# BSPD_Final_1.net
KiCad netlist of a schematic drawn in EAGLE
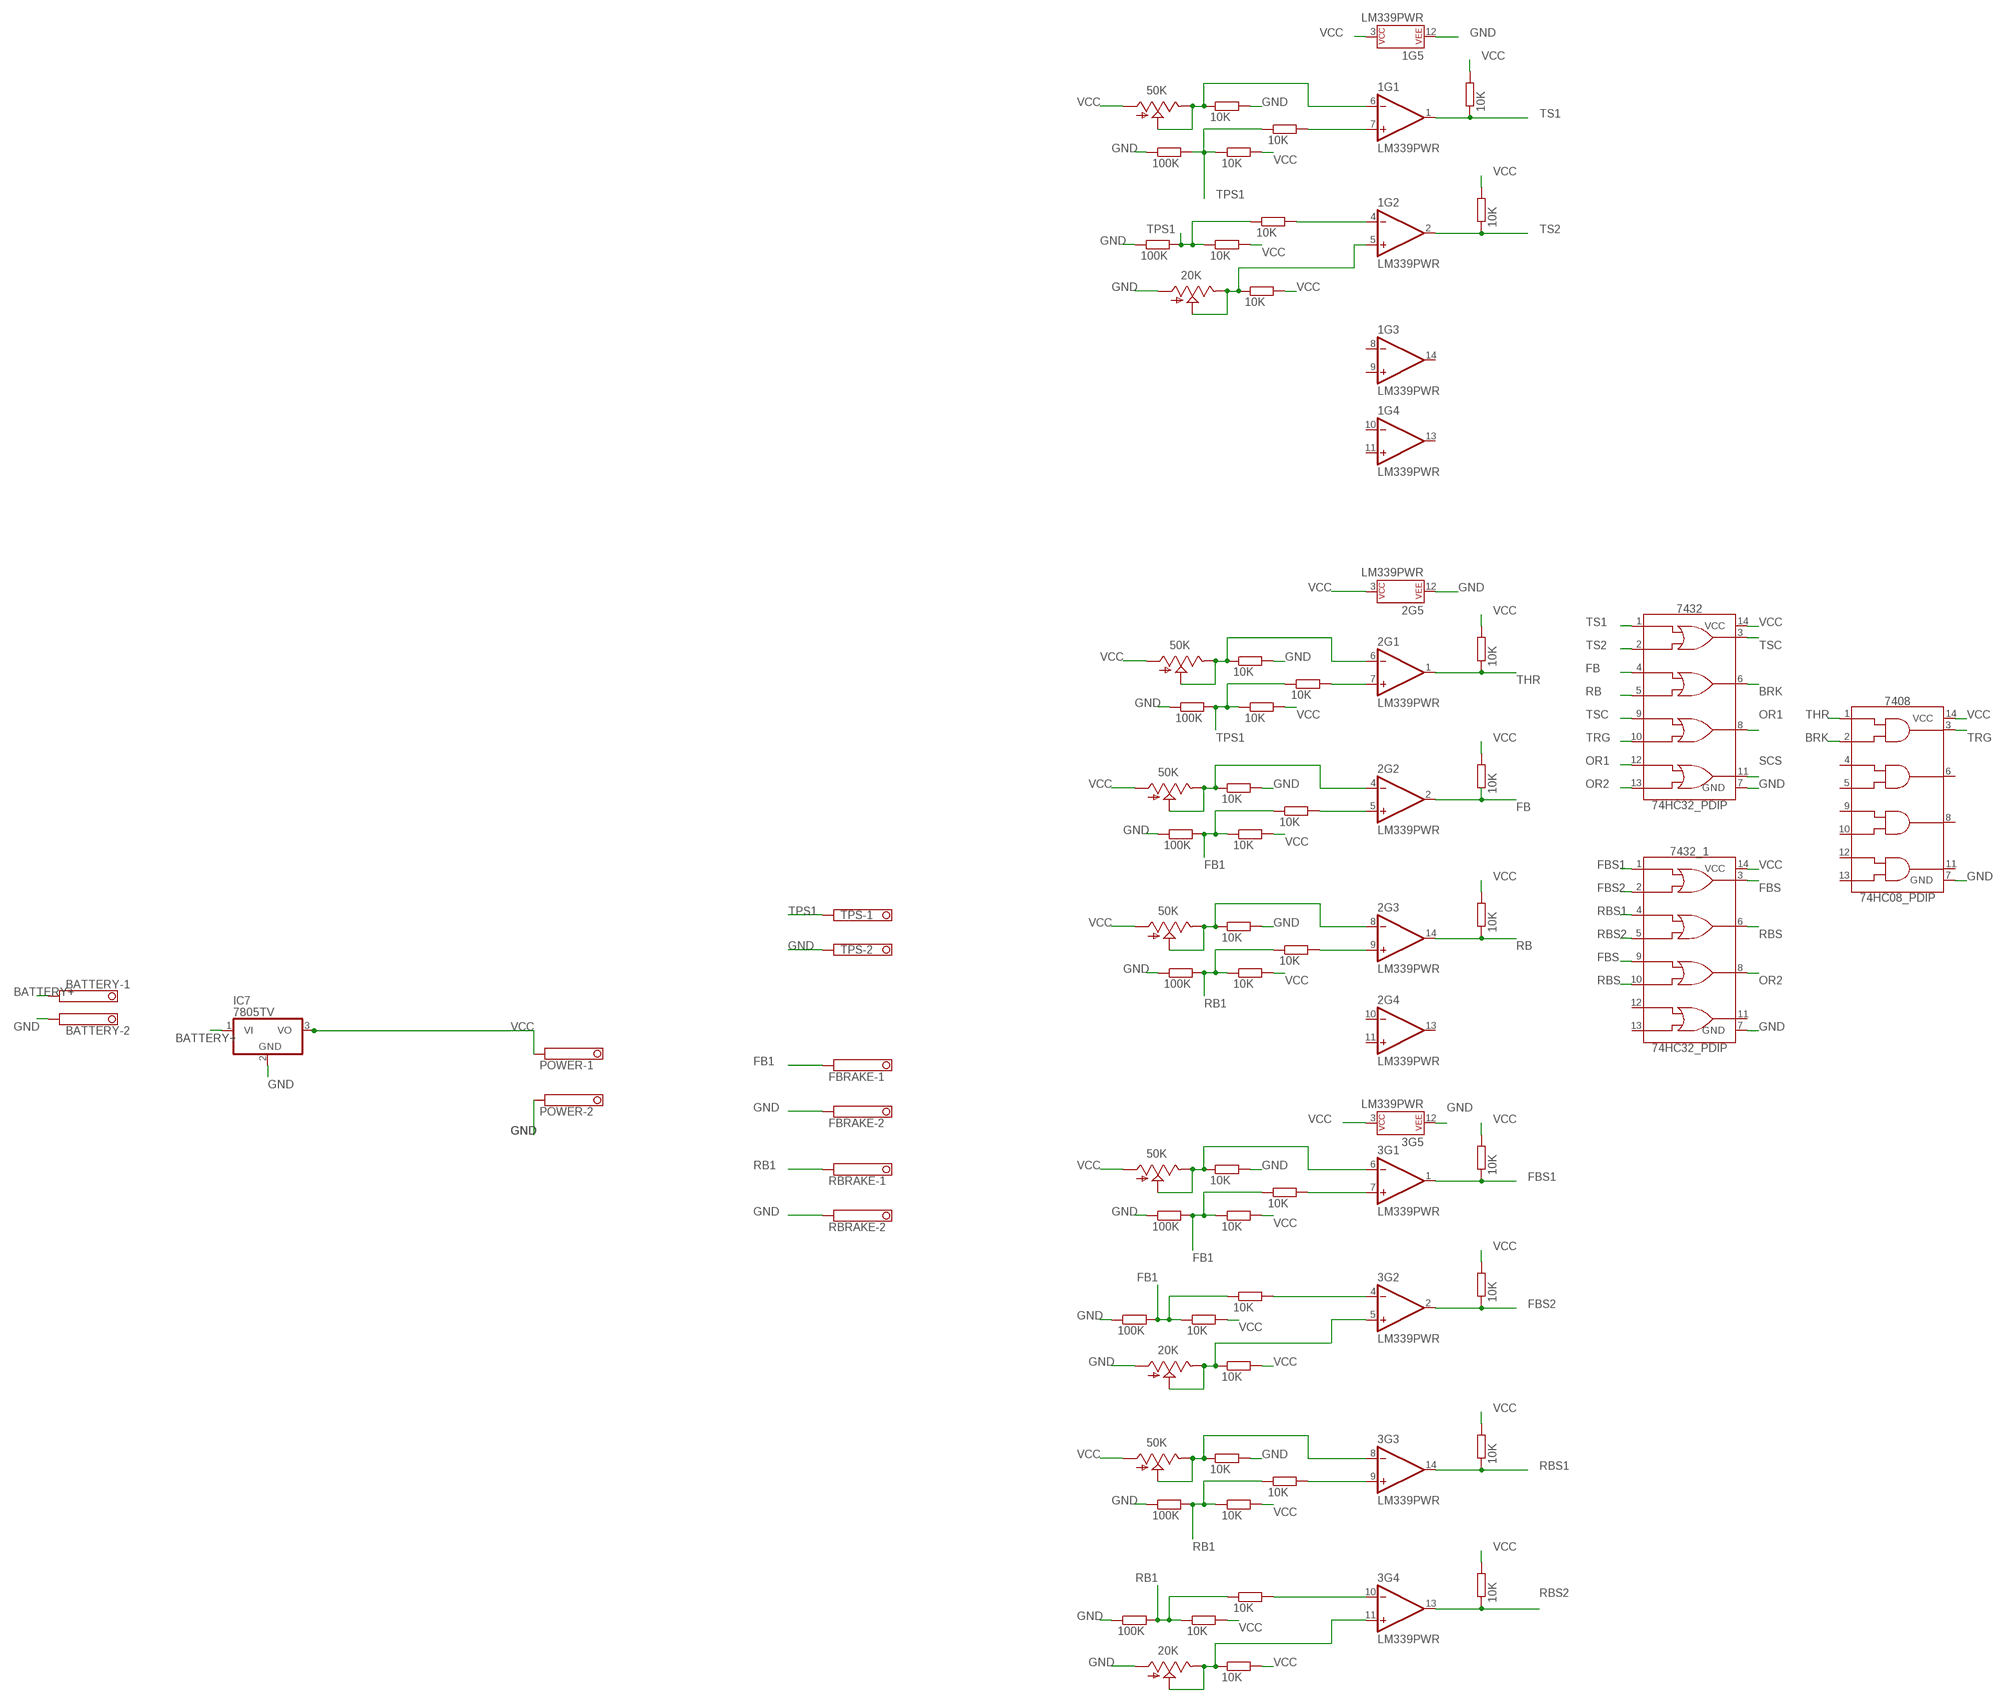
[diagram p0: schematic, sheet 1, part 1 of 2]
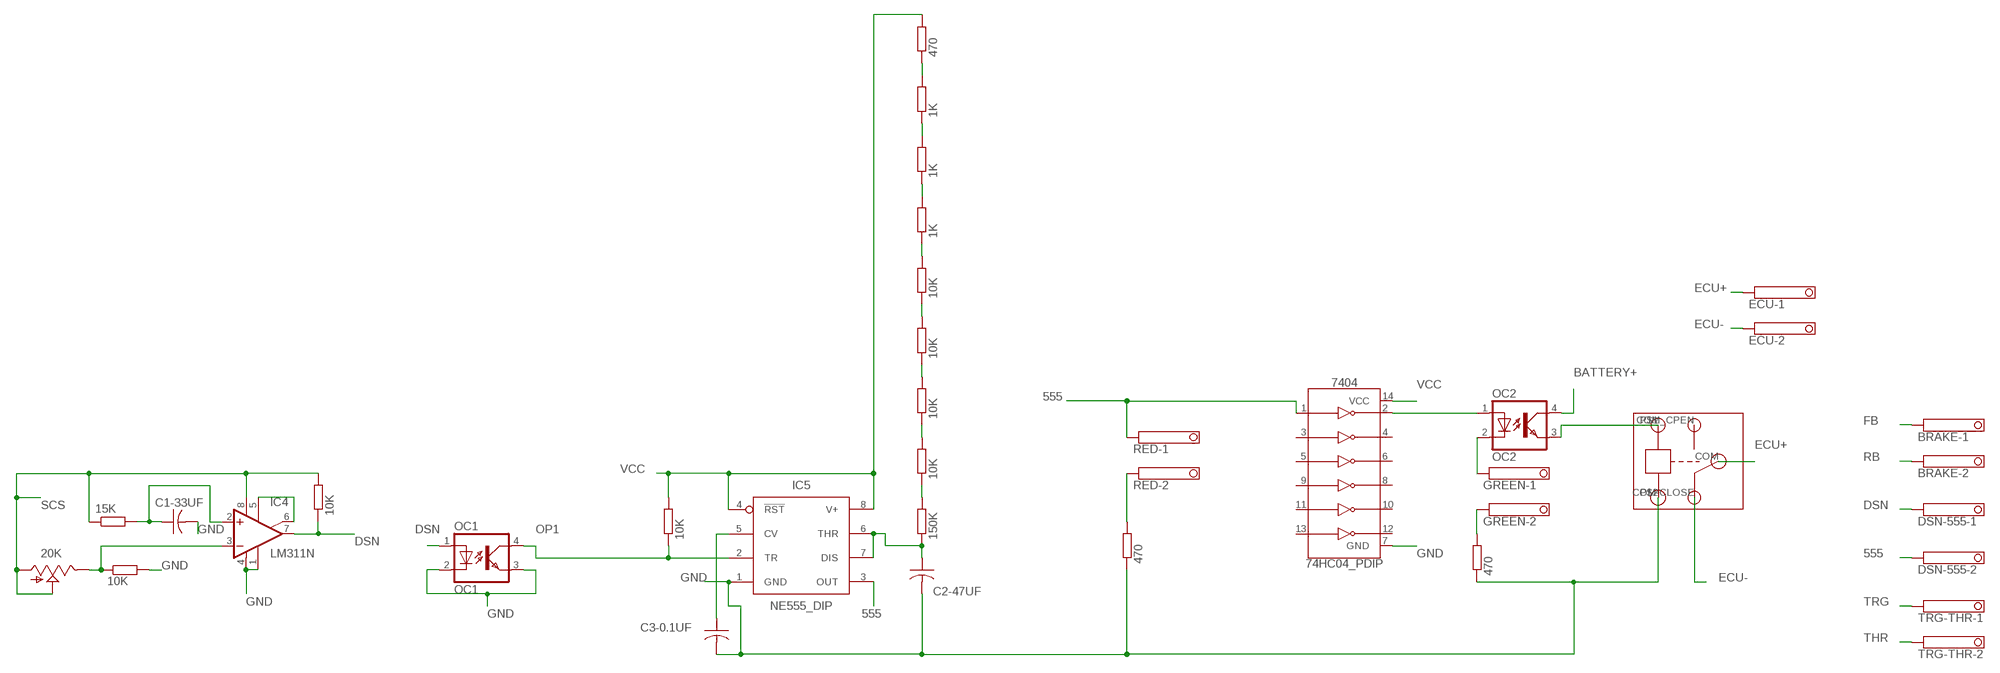
[diagram p1: schematic, sheet 1, part 2 of 2]

(export (version "E")
  (design (tool "Eeschema 10.0.6"))
  (components
    (comp (ref "1")
      (value "LM339PWR")
      (footprint "eagle-import:TSSOP-14")
      (libsource (lib "eagle-import") (part "LM339"))
    )
    (comp (ref "2")
      (value "LM339PWR")
      (footprint "eagle-import:TSSOP-14")
      (libsource (lib "eagle-import") (part "LM339"))
    )
    (comp (ref "3")
      (value "LM339PWR")
      (footprint "eagle-import:TSSOP-14")
      (libsource (lib "eagle-import") (part "LM339"))
    )
    (comp (ref "50K9")
      (value "20K")
      (footprint "eagle-import:B64Y")
      (libsource (lib "eagle-import") (part "TRIM_US-B64Y"))
    )
    (comp (ref "555RES1")
      (value "150K")
      (footprint "eagle-import:0207_10")
      (libsource (lib "eagle-import") (part "R-EU_0207/10"))
    )
    (comp (ref "555RES2")
      (value "10K")
      (footprint "eagle-import:0207_10")
      (libsource (lib "eagle-import") (part "R-EU_0207/10"))
    )
    (comp (ref "555RES3")
      (value "10K")
      (footprint "eagle-import:0207_10")
      (libsource (lib "eagle-import") (part "R-EU_0207/10"))
    )
    (comp (ref "555RES4")
      (value "10K")
      (footprint "eagle-import:0207_10")
      (libsource (lib "eagle-import") (part "R-EU_0207/10"))
    )
    (comp (ref "555RES5")
      (value "10K")
      (footprint "eagle-import:0207_10")
      (libsource (lib "eagle-import") (part "R-EU_0207/10"))
    )
    (comp (ref "555RES6")
      (value "1K")
      (footprint "eagle-import:0207_10")
      (libsource (lib "eagle-import") (part "R-EU_0207/10"))
    )
    (comp (ref "555RES7")
      (value "1K")
      (footprint "eagle-import:0207_10")
      (libsource (lib "eagle-import") (part "R-EU_0207/10"))
    )
    (comp (ref "555RES8")
      (value "1K")
      (footprint "eagle-import:0207_10")
      (libsource (lib "eagle-import") (part "R-EU_0207/10"))
    )
    (comp (ref "555RES9")
      (value "470")
      (footprint "eagle-import:0207_10")
      (libsource (lib "eagle-import") (part "R-EU_0207/10"))
    )
    (comp (ref "7404")
      (value "74HC04_PDIP")
      (footprint "eagle-import:DIP762W53P254L1969H508Q14B")
      (fields (field (name "MANUFACTURER") "Generic"))
      (libsource (lib "eagle-import") (part "74HC04_PDIP"))
    )
    (comp (ref "7408")
      (value "74HC08_PDIP")
      (footprint "eagle-import:DIP762W53P254L1969H508Q14B")
      (fields (field (name "MANUFACTURER") "Generic"))
      (libsource (lib "eagle-import") (part "74HC08_PDIP"))
    )
    (comp (ref "7432")
      (value "74HC32_PDIP")
      (footprint "eagle-import:DIP762W53P254L1969H508Q14B")
      (fields (field (name "MANUFACTURER") "Generic"))
      (libsource (lib "eagle-import") (part "74HC32_PDIP"))
    )
    (comp (ref "7432_1")
      (value "74HC32_PDIP")
      (footprint "eagle-import:DIP762W53P254L1969H508Q14B")
      (fields (field (name "MANUFACTURER") "Generic"))
      (libsource (lib "eagle-import") (part "74HC32_PDIP"))
    )
    (comp (ref "BATTERY")
      (value "TERMINAL-BLOCK-3.5MM-2-PIN-ROUND-PAD")
      (footprint "eagle-import:TERMINAL-BLOCK-2-PIN-3.5MM-ROUND-PAD")
      (libsource (lib "eagle-import") (part "TERMINAL-BLOCK-3.5MM-2-PIN-ROUND-PAD"))
    )
    (comp (ref "BRAKE")
      (value "TERMINAL-BLOCK-3.5MM-2-PIN-ROUND-PAD")
      (footprint "eagle-import:TERMINAL-BLOCK-2-PIN-3.5MM-ROUND-PAD")
      (libsource (lib "eagle-import") (part "TERMINAL-BLOCK-3.5MM-2-PIN-ROUND-PAD"))
    )
    (comp (ref "C1-33UF")
      (value "33uF")
      (footprint "eagle-import:CAP_RADIAL_2MM")
      (fields
        (field (name "DIGIKEY_PART_NUMBER") "P5179-ND")
        (field (name "MANUFACTURER") "Panasonic Electronic Components")
        (field (name "MPN") "ECA-1HM220")
        (field (name "CREATED_BY") "PCBLayout.com")
      )
      (libsource (lib "eagle-import") (part "ECA-1HM220"))
    )
    (comp (ref "C2-47UF")
      (value "33uF")
      (footprint "eagle-import:CAP_RADIAL_2MM")
      (fields
        (field (name "DIGIKEY_PART_NUMBER") "P5179-ND")
        (field (name "MANUFACTURER") "Panasonic Electronic Components")
        (field (name "MPN") "ECA-1HM220")
        (field (name "CREATED_BY") "PCBLayout.com")
      )
      (libsource (lib "eagle-import") (part "ECA-1HM220"))
    )
    (comp (ref "C3-0.1UF")
      (value "33uF")
      (footprint "eagle-import:CAP_RADIAL_2MM")
      (fields
        (field (name "DIGIKEY_PART_NUMBER") "P5179-ND")
        (field (name "MANUFACTURER") "Panasonic Electronic Components")
        (field (name "MPN") "ECA-1HM220")
        (field (name "CREATED_BY") "PCBLayout.com")
      )
      (libsource (lib "eagle-import") (part "ECA-1HM220"))
    )
    (comp (ref "DCNPULL")
      (value "10K")
      (footprint "eagle-import:0207_10")
      (libsource (lib "eagle-import") (part "R-EU_0207/10"))
    )
    (comp (ref "DCNRES1")
      (value "15K")
      (footprint "eagle-import:0207_10")
      (libsource (lib "eagle-import") (part "R-EU_0207/10"))
    )
    (comp (ref "DCNRES2")
      (value "10K")
      (footprint "eagle-import:0207_10")
      (libsource (lib "eagle-import") (part "R-EU_0207/10"))
    )
    (comp (ref "DSN-555")
      (value "TERMINAL-BLOCK-3.5MM-2-PIN-ROUND-PAD")
      (footprint "eagle-import:TERMINAL-BLOCK-2-PIN-3.5MM-ROUND-PAD")
      (libsource (lib "eagle-import") (part "TERMINAL-BLOCK-3.5MM-2-PIN-ROUND-PAD"))
    )
    (comp (ref "ECU")
      (value "TERMINAL-BLOCK-3.5MM-2-PIN-ROUND-PAD")
      (footprint "eagle-import:TERMINAL-BLOCK-2-PIN-3.5MM-ROUND-PAD")
      (libsource (lib "eagle-import") (part "TERMINAL-BLOCK-3.5MM-2-PIN-ROUND-PAD"))
    )
    (comp (ref "FBRAKE")
      (value "TERMINAL-BLOCK-3.5MM-2-PIN-ROUND-PAD")
      (footprint "eagle-import:TERMINAL-BLOCK-2-PIN-3.5MM-ROUND-PAD")
      (libsource (lib "eagle-import") (part "TERMINAL-BLOCK-3.5MM-2-PIN-ROUND-PAD"))
    )
    (comp (ref "GREEN")
      (value "TERMINAL-BLOCK-3.5MM-2-PIN-ROUND-PAD")
      (footprint "eagle-import:TERMINAL-BLOCK-2-PIN-3.5MM-ROUND-PAD")
      (libsource (lib "eagle-import") (part "TERMINAL-BLOCK-3.5MM-2-PIN-ROUND-PAD"))
    )
    (comp (ref "IC4")
      (value "LM311N")
      (footprint "eagle-import:DIL08")
      (libsource (lib "eagle-import") (part "LM311N"))
    )
    (comp (ref "IC5")
      (value "NE555_DIP")
      (footprint "eagle-import:DIP826W53P254L959H508Q8B")
      (fields (field (name "MANUFACTURER") "Texas Instruments ") (field (name "MPN") "NE555P "))
      (libsource (lib "eagle-import") (part "555_DIPNE"))
    )
    (comp (ref "IC7")
      (value "7805TV")
      (footprint "eagle-import:TO220V")
      (libsource (lib "eagle-import") (part "78TV05"))
    )
    (comp (ref "OC1")
      (value "OC1")
      (footprint "eagle-import:DIL04")
      (libsource (lib "eagle-import") (part "PC817"))
    )
    (comp (ref "OC2")
      (value "OC2")
      (footprint "eagle-import:DIL04")
      (libsource (lib "eagle-import") (part "PC817"))
    )
    (comp (ref "OCTPULL")
      (value "10K")
      (footprint "eagle-import:0207_10")
      (libsource (lib "eagle-import") (part "R-EU_0207/10"))
    )
    (comp (ref "POT1")
      (value "50K")
      (footprint "eagle-import:B64Y")
      (libsource (lib "eagle-import") (part "TRIM_US-B64Y"))
    )
    (comp (ref "POT2")
      (value "20K")
      (footprint "eagle-import:B64Y")
      (libsource (lib "eagle-import") (part "TRIM_US-B64Y"))
    )
    (comp (ref "POT3")
      (value "50K")
      (footprint "eagle-import:B64Y")
      (libsource (lib "eagle-import") (part "TRIM_US-B64Y"))
    )
    (comp (ref "POT4")
      (value "50K")
      (footprint "eagle-import:B64Y")
      (libsource (lib "eagle-import") (part "TRIM_US-B64Y"))
    )
    (comp (ref "POT5")
      (value "50K")
      (footprint "eagle-import:B64Y")
      (libsource (lib "eagle-import") (part "TRIM_US-B64Y"))
    )
    (comp (ref "POT6")
      (value "50K")
      (footprint "eagle-import:B64Y")
      (libsource (lib "eagle-import") (part "TRIM_US-B64Y"))
    )
    (comp (ref "POT7")
      (value "20K")
      (footprint "eagle-import:B64Y")
      (libsource (lib "eagle-import") (part "TRIM_US-B64Y"))
    )
    (comp (ref "POT8")
      (value "50K")
      (footprint "eagle-import:B64Y")
      (libsource (lib "eagle-import") (part "TRIM_US-B64Y"))
    )
    (comp (ref "POT9")
      (value "20K")
      (footprint "eagle-import:B64Y")
      (libsource (lib "eagle-import") (part "TRIM_US-B64Y"))
    )
    (comp (ref "POWER")
      (value "TERMINAL-BLOCK-3.5MM-2-PIN-ROUND-PAD")
      (footprint "eagle-import:TERMINAL-BLOCK-2-PIN-3.5MM-ROUND-PAD")
      (libsource (lib "eagle-import") (part "TERMINAL-BLOCK-3.5MM-2-PIN-ROUND-PAD"))
    )
    (comp (ref "PULL1")
      (value "10K")
      (footprint "eagle-import:0207_10")
      (libsource (lib "eagle-import") (part "R-EU_0207/10"))
    )
    (comp (ref "PULL2")
      (value "10K")
      (footprint "eagle-import:0207_10")
      (libsource (lib "eagle-import") (part "R-EU_0207/10"))
    )
    (comp (ref "PULL3")
      (value "10K")
      (footprint "eagle-import:0207_10")
      (libsource (lib "eagle-import") (part "R-EU_0207/10"))
    )
    (comp (ref "PULL4")
      (value "10K")
      (footprint "eagle-import:0207_10")
      (libsource (lib "eagle-import") (part "R-EU_0207/10"))
    )
    (comp (ref "PULL5")
      (value "10K")
      (footprint "eagle-import:0207_10")
      (libsource (lib "eagle-import") (part "R-EU_0207/10"))
    )
    (comp (ref "PULL6")
      (value "10K")
      (footprint "eagle-import:0207_10")
      (libsource (lib "eagle-import") (part "R-EU_0207/10"))
    )
    (comp (ref "PULL7")
      (value "10K")
      (footprint "eagle-import:0207_10")
      (libsource (lib "eagle-import") (part "R-EU_0207/10"))
    )
    (comp (ref "PULL8")
      (value "10K")
      (footprint "eagle-import:0207_10")
      (libsource (lib "eagle-import") (part "R-EU_0207/10"))
    )
    (comp (ref "PULL9")
      (value "10K")
      (footprint "eagle-import:0207_10")
      (libsource (lib "eagle-import") (part "R-EU_0207/10"))
    )
    (comp (ref "R56")
      (value "470")
      (footprint "eagle-import:0207_10")
      (libsource (lib "eagle-import") (part "R-EU_0207/10"))
    )
    (comp (ref "R57")
      (value "470")
      (footprint "eagle-import:0207_10")
      (libsource (lib "eagle-import") (part "R-EU_0207/10"))
    )
    (comp (ref "RBRAKE")
      (value "TERMINAL-BLOCK-3.5MM-2-PIN-ROUND-PAD")
      (footprint "eagle-import:TERMINAL-BLOCK-2-PIN-3.5MM-ROUND-PAD")
      (libsource (lib "eagle-import") (part "TERMINAL-BLOCK-3.5MM-2-PIN-ROUND-PAD"))
    )
    (comp (ref "RED")
      (value "TERMINAL-BLOCK-3.5MM-2-PIN-ROUND-PAD")
      (footprint "eagle-import:TERMINAL-BLOCK-2-PIN-3.5MM-ROUND-PAD")
      (libsource (lib "eagle-import") (part "TERMINAL-BLOCK-3.5MM-2-PIN-ROUND-PAD"))
    )
    (comp (ref "RES11")
      (value "10K")
      (footprint "eagle-import:0207_10")
      (libsource (lib "eagle-import") (part "R-EU_0207/10"))
    )
    (comp (ref "RES12")
      (value "10K")
      (footprint "eagle-import:0207_10")
      (libsource (lib "eagle-import") (part "R-EU_0207/10"))
    )
    (comp (ref "RES13")
      (value "100K")
      (footprint "eagle-import:0207_10")
      (libsource (lib "eagle-import") (part "R-EU_0207/10"))
    )
    (comp (ref "RES14")
      (value "10K")
      (footprint "eagle-import:0207_10")
      (libsource (lib "eagle-import") (part "R-EU_0207/10"))
    )
    (comp (ref "RES21")
      (value "10K")
      (footprint "eagle-import:0207_10")
      (libsource (lib "eagle-import") (part "R-EU_0207/10"))
    )
    (comp (ref "RES22")
      (value "10K")
      (footprint "eagle-import:0207_10")
      (libsource (lib "eagle-import") (part "R-EU_0207/10"))
    )
    (comp (ref "RES23")
      (value "10K")
      (footprint "eagle-import:0207_10")
      (libsource (lib "eagle-import") (part "R-EU_0207/10"))
    )
    (comp (ref "RES24")
      (value "100K")
      (footprint "eagle-import:0207_10")
      (libsource (lib "eagle-import") (part "R-EU_0207/10"))
    )
    (comp (ref "RES31")
      (value "10K")
      (footprint "eagle-import:0207_10")
      (libsource (lib "eagle-import") (part "R-EU_0207/10"))
    )
    (comp (ref "RES32")
      (value "10K")
      (footprint "eagle-import:0207_10")
      (libsource (lib "eagle-import") (part "R-EU_0207/10"))
    )
    (comp (ref "RES33")
      (value "100K")
      (footprint "eagle-import:0207_10")
      (libsource (lib "eagle-import") (part "R-EU_0207/10"))
    )
    (comp (ref "RES34")
      (value "10K")
      (footprint "eagle-import:0207_10")
      (libsource (lib "eagle-import") (part "R-EU_0207/10"))
    )
    (comp (ref "RES41")
      (value "10K")
      (footprint "eagle-import:0207_10")
      (libsource (lib "eagle-import") (part "R-EU_0207/10"))
    )
    (comp (ref "RES42")
      (value "10K")
      (footprint "eagle-import:0207_10")
      (libsource (lib "eagle-import") (part "R-EU_0207/10"))
    )
    (comp (ref "RES43")
      (value "100K")
      (footprint "eagle-import:0207_10")
      (libsource (lib "eagle-import") (part "R-EU_0207/10"))
    )
    (comp (ref "RES44")
      (value "10K")
      (footprint "eagle-import:0207_10")
      (libsource (lib "eagle-import") (part "R-EU_0207/10"))
    )
    (comp (ref "RES51")
      (value "10K")
      (footprint "eagle-import:0207_10")
      (libsource (lib "eagle-import") (part "R-EU_0207/10"))
    )
    (comp (ref "RES52")
      (value "10K")
      (footprint "eagle-import:0207_10")
      (libsource (lib "eagle-import") (part "R-EU_0207/10"))
    )
    (comp (ref "RES53")
      (value "100K")
      (footprint "eagle-import:0207_10")
      (libsource (lib "eagle-import") (part "R-EU_0207/10"))
    )
    (comp (ref "RES54")
      (value "10K")
      (footprint "eagle-import:0207_10")
      (libsource (lib "eagle-import") (part "R-EU_0207/10"))
    )
    (comp (ref "RES61")
      (value "10K")
      (footprint "eagle-import:0207_10")
      (libsource (lib "eagle-import") (part "R-EU_0207/10"))
    )
    (comp (ref "RES62")
      (value "10K")
      (footprint "eagle-import:0207_10")
      (libsource (lib "eagle-import") (part "R-EU_0207/10"))
    )
    (comp (ref "RES63")
      (value "100K")
      (footprint "eagle-import:0207_10")
      (libsource (lib "eagle-import") (part "R-EU_0207/10"))
    )
    (comp (ref "RES64")
      (value "10K")
      (footprint "eagle-import:0207_10")
      (libsource (lib "eagle-import") (part "R-EU_0207/10"))
    )
    (comp (ref "RES71")
      (value "10K")
      (footprint "eagle-import:0207_10")
      (libsource (lib "eagle-import") (part "R-EU_0207/10"))
    )
    (comp (ref "RES72")
      (value "10K")
      (footprint "eagle-import:0207_10")
      (libsource (lib "eagle-import") (part "R-EU_0207/10"))
    )
    (comp (ref "RES73")
      (value "100K")
      (footprint "eagle-import:0207_10")
      (libsource (lib "eagle-import") (part "R-EU_0207/10"))
    )
    (comp (ref "RES74")
      (value "10K")
      (footprint "eagle-import:0207_10")
      (libsource (lib "eagle-import") (part "R-EU_0207/10"))
    )
    (comp (ref "RES81")
      (value "10K")
      (footprint "eagle-import:0207_10")
      (libsource (lib "eagle-import") (part "R-EU_0207/10"))
    )
    (comp (ref "RES82")
      (value "10K")
      (footprint "eagle-import:0207_10")
      (libsource (lib "eagle-import") (part "R-EU_0207/10"))
    )
    (comp (ref "RES83")
      (value "100K")
      (footprint "eagle-import:0207_10")
      (libsource (lib "eagle-import") (part "R-EU_0207/10"))
    )
    (comp (ref "RES84")
      (value "10K")
      (footprint "eagle-import:0207_10")
      (libsource (lib "eagle-import") (part "R-EU_0207/10"))
    )
    (comp (ref "RES91")
      (value "10K")
      (footprint "eagle-import:0207_10")
      (libsource (lib "eagle-import") (part "R-EU_0207/10"))
    )
    (comp (ref "RES92")
      (value "10K")
      (footprint "eagle-import:0207_10")
      (libsource (lib "eagle-import") (part "R-EU_0207/10"))
    )
    (comp (ref "RES93")
      (value "100K")
      (footprint "eagle-import:0207_10")
      (libsource (lib "eagle-import") (part "R-EU_0207/10"))
    )
    (comp (ref "RES94")
      (value "10K")
      (footprint "eagle-import:0207_10")
      (libsource (lib "eagle-import") (part "R-EU_0207/10"))
    )
    (comp (ref "TPS")
      (value "TERMINAL-BLOCK-3.5MM-2-PIN-ROUND-PAD")
      (footprint "eagle-import:TERMINAL-BLOCK-2-PIN-3.5MM-ROUND-PAD")
      (libsource (lib "eagle-import") (part "Rembrandt_Electronics_-_Terminal_Block_3-5mm_v1-0_TERMINAL-BLOCK-3.5MM-2-PIN-ROUND-PAD"))
    )
    (comp (ref "TRG-THR")
      (value "TERMINAL-BLOCK-3.5MM-2-PIN-ROUND-PAD")
      (footprint "eagle-import:TERMINAL-BLOCK-2-PIN-3.5MM-ROUND-PAD")
      (libsource (lib "eagle-import") (part "TERMINAL-BLOCK-3.5MM-2-PIN-ROUND-PAD"))
    )
    (comp (ref "U$1")
      (value "RELAY")
      (footprint "eagle-import:RELAY")
      (libsource (lib "eagle-import") (part "RELAY"))
    )
  )
  (nets
    (net (code "1") (name "/555") (class "Default")
      (node (ref "7404") (pin "1") (pinfunction "1A_1") (pintype "input"))
      (node (ref "DSN-555") (pin "2") (pinfunction "K_2") (pintype "passive"))
      (node (ref "IC5") (pin "3") (pinfunction "OUT_3") (pintype "output"))
      (node (ref "RED") (pin "1") (pinfunction "K_1") (pintype "passive"))
    )
    (net (code "2") (name "/BATTERY+") (class "Default")
      (node (ref "BATTERY") (pin "1") (pinfunction "K_1") (pintype "passive"))
      (node (ref "IC7") (pin "1") (pinfunction "VI_1") (pintype "input"))
      (node (ref "OC2") (pin "4") (pinfunction "COL_4") (pintype "passive"))
    )
    (net (code "3") (name "/BRK") (class "Default")
      (node (ref "7408") (pin "2") (pinfunction "1B_2") (pintype "input"))
      (node (ref "7432") (pin "6") (pinfunction "2Y_6") (pintype "output"))
    )
    (net (code "4") (name "/DSN") (class "Default")
      (node (ref "DCNPULL") (pin "1") (pinfunction "1_1") (pintype "passive"))
      (node (ref "DSN-555") (pin "1") (pinfunction "K_1") (pintype "passive"))
      (node (ref "IC4") (pin "7") (pinfunction "OUT_7") (pintype "output"))
      (node (ref "OC1") (pin "1") (pinfunction "A_1") (pintype "passive"))
    )
    (net (code "5") (name "/ECU+") (class "Default")
      (node (ref "ECU") (pin "1") (pinfunction "K_1") (pintype "passive"))
      (node (ref "U$1") (pin "COM") (pinfunction "COM_COM") (pintype "bidirectional"))
    )
    (net (code "6") (name "/ECU-") (class "Default")
      (node (ref "ECU") (pin "2") (pinfunction "K_2") (pintype "passive"))
      (node (ref "U$1") (pin "COM-CLOSE") (pinfunction "COM-CLOSE_COM-CLOSE") (pintype "bidirectional"))
    )
    (net (code "7") (name "/FB") (class "Default")
      (node (ref "2") (pin "2") (pinfunction "OUT_2") (pintype "output"))
      (node (ref "7432") (pin "4") (pinfunction "2A_4") (pintype "input"))
      (node (ref "BRAKE") (pin "1") (pinfunction "K_1") (pintype "passive"))
      (node (ref "PULL4") (pin "1") (pinfunction "1_1") (pintype "passive"))
    )
    (net (code "8") (name "/FB1") (class "Default")
      (node (ref "FBRAKE") (pin "1") (pinfunction "K_1") (pintype "passive"))
      (node (ref "RES41") (pin "1") (pinfunction "1_1") (pintype "passive"))
      (node (ref "RES42") (pin "1") (pinfunction "1_1") (pintype "passive"))
      (node (ref "RES43") (pin "2") (pinfunction "2_2") (pintype "passive"))
      (node (ref "RES61") (pin "1") (pinfunction "1_1") (pintype "passive"))
      (node (ref "RES62") (pin "1") (pinfunction "1_1") (pintype "passive"))
      (node (ref "RES63") (pin "2") (pinfunction "2_2") (pintype "passive"))
      (node (ref "RES71") (pin "1") (pinfunction "1_1") (pintype "passive"))
      (node (ref "RES72") (pin "1") (pinfunction "1_1") (pintype "passive"))
      (node (ref "RES73") (pin "2") (pinfunction "2_2") (pintype "passive"))
    )
    (net (code "9") (name "/FBS") (class "Default")
      (node (ref "7432_1") (pin "3") (pinfunction "1Y_3") (pintype "output"))
      (node (ref "7432_1") (pin "9") (pinfunction "3A_9") (pintype "input"))
    )
    (net (code "10") (name "/FBS1") (class "Default")
      (node (ref "3") (pin "1") (pinfunction "OUT_1") (pintype "output"))
      (node (ref "7432_1") (pin "1") (pinfunction "1A_1") (pintype "input"))
      (node (ref "PULL6") (pin "1") (pinfunction "1_1") (pintype "passive"))
    )
    (net (code "11") (name "/FBS2") (class "Default")
      (node (ref "3") (pin "2") (pinfunction "OUT_2") (pintype "output"))
      (node (ref "7432_1") (pin "2") (pinfunction "1B_2") (pintype "input"))
      (node (ref "PULL7") (pin "1") (pinfunction "1_1") (pintype "passive"))
    )
    (net (code "12") (name "/GND") (class "Default")
      (node (ref "1") (pin "12") (pinfunction "P$V-_12") (pintype "bidirectional"))
      (node (ref "2") (pin "12") (pinfunction "P$V-_12") (pintype "bidirectional"))
      (node (ref "3") (pin "12") (pinfunction "P$V-_12") (pintype "bidirectional"))
      (node (ref "7404") (pin "7") (pinfunction "GND_7") (pintype "bidirectional"))
      (node (ref "7408") (pin "7") (pinfunction "GND_7") (pintype "bidirectional"))
      (node (ref "7432") (pin "7") (pinfunction "GND_7") (pintype "bidirectional"))
      (node (ref "7432_1") (pin "7") (pinfunction "GND_7") (pintype "bidirectional"))
      (node (ref "BATTERY") (pin "2") (pinfunction "K_2") (pintype "passive"))
      (node (ref "C1-33UF") (pin "2") (pinfunction "2_2") (pintype "passive"))
      (node (ref "C2-47UF") (pin "2") (pinfunction "2_2") (pintype "passive"))
      (node (ref "C3-0.1UF") (pin "2") (pinfunction "2_2") (pintype "passive"))
      (node (ref "DCNRES2") (pin "2") (pinfunction "2_2") (pintype "passive"))
      (node (ref "FBRAKE") (pin "2") (pinfunction "K_2") (pintype "passive"))
      (node (ref "IC4") (pin "1") (pinfunction "GND_1") (pintype "passive"))
      (node (ref "IC4") (pin "4") (pinfunction "V-_4") (pintype "power_in"))
      (node (ref "IC5") (pin "1") (pinfunction "GND_1") (pintype "power_in"))
      (node (ref "IC7") (pin "2") (pinfunction "GND_2") (pintype "passive"))
      (node (ref "OC1") (pin "2") (pinfunction "C_2") (pintype "passive"))
      (node (ref "OC1") (pin "3") (pinfunction "EMIT_3") (pintype "passive"))
      (node (ref "POT2") (pin "A") (pinfunction "A_A") (pintype "passive"))
      (node (ref "POT7") (pin "A") (pinfunction "A_A") (pintype "passive"))
      (node (ref "POT9") (pin "A") (pinfunction "A_A") (pintype "passive"))
      (node (ref "POWER") (pin "2") (pinfunction "K_2") (pintype "passive"))
      (node (ref "R56") (pin "1") (pinfunction "1_1") (pintype "passive"))
      (node (ref "R57") (pin "1") (pinfunction "1_1") (pintype "passive"))
      (node (ref "RBRAKE") (pin "2") (pinfunction "K_2") (pintype "passive"))
      (node (ref "RES13") (pin "1") (pinfunction "1_1") (pintype "passive"))
      (node (ref "RES14") (pin "2") (pinfunction "2_2") (pintype "passive"))
      (node (ref "RES24") (pin "1") (pinfunction "1_1") (pintype "passive"))
      (node (ref "RES33") (pin "1") (pinfunction "1_1") (pintype "passive"))
      (node (ref "RES34") (pin "2") (pinfunction "2_2") (pintype "passive"))
      (node (ref "RES43") (pin "1") (pinfunction "1_1") (pintype "passive"))
      (node (ref "RES44") (pin "2") (pinfunction "2_2") (pintype "passive"))
      (node (ref "RES53") (pin "1") (pinfunction "1_1") (pintype "passive"))
      (node (ref "RES54") (pin "2") (pinfunction "2_2") (pintype "passive"))
      (node (ref "RES63") (pin "1") (pinfunction "1_1") (pintype "passive"))
      (node (ref "RES64") (pin "2") (pinfunction "2_2") (pintype "passive"))
      (node (ref "RES73") (pin "1") (pinfunction "1_1") (pintype "passive"))
      (node (ref "RES83") (pin "1") (pinfunction "1_1") (pintype "passive"))
      (node (ref "RES84") (pin "2") (pinfunction "2_2") (pintype "passive"))
      (node (ref "RES93") (pin "1") (pinfunction "1_1") (pintype "passive"))
      (node (ref "TPS") (pin "2") (pinfunction "K_2") (pintype "passive"))
      (node (ref "U$1") (pin "P$2") (pinfunction "GND_P$2") (pintype "bidirectional"))
    )
    (net (code "13") (name "/OP1") (class "Default")
      (node (ref "IC5") (pin "2") (pinfunction "TR_2") (pintype "input"))
      (node (ref "OC1") (pin "4") (pinfunction "COL_4") (pintype "passive"))
      (node (ref "OCTPULL") (pin "1") (pinfunction "1_1") (pintype "passive"))
    )
    (net (code "14") (name "/OR1") (class "Default")
      (node (ref "7432") (pin "12") (pinfunction "4A_12") (pintype "input"))
      (node (ref "7432") (pin "8") (pinfunction "3Y_8") (pintype "output"))
    )
    (net (code "15") (name "/OR2") (class "Default")
      (node (ref "7432") (pin "13") (pinfunction "4B_13") (pintype "input"))
      (node (ref "7432_1") (pin "8") (pinfunction "3Y_8") (pintype "output"))
    )
    (net (code "16") (name "/RB") (class "Default")
      (node (ref "2") (pin "14") (pinfunction "OUT_14") (pintype "output"))
      (node (ref "7432") (pin "5") (pinfunction "2B_5") (pintype "input"))
      (node (ref "BRAKE") (pin "2") (pinfunction "K_2") (pintype "passive"))
      (node (ref "PULL5") (pin "1") (pinfunction "1_1") (pintype "passive"))
    )
    (net (code "17") (name "/RB1") (class "Default")
      (node (ref "RBRAKE") (pin "1") (pinfunction "K_1") (pintype "passive"))
      (node (ref "RES51") (pin "1") (pinfunction "1_1") (pintype "passive"))
      (node (ref "RES52") (pin "1") (pinfunction "1_1") (pintype "passive"))
      (node (ref "RES53") (pin "2") (pinfunction "2_2") (pintype "passive"))
      (node (ref "RES81") (pin "1") (pinfunction "1_1") (pintype "passive"))
      (node (ref "RES82") (pin "1") (pinfunction "1_1") (pintype "passive"))
      (node (ref "RES83") (pin "2") (pinfunction "2_2") (pintype "passive"))
      (node (ref "RES91") (pin "1") (pinfunction "1_1") (pintype "passive"))
      (node (ref "RES92") (pin "1") (pinfunction "1_1") (pintype "passive"))
      (node (ref "RES93") (pin "2") (pinfunction "2_2") (pintype "passive"))
    )
    (net (code "18") (name "/RBS") (class "Default")
      (node (ref "7432_1") (pin "10") (pinfunction "3B_10") (pintype "input"))
      (node (ref "7432_1") (pin "6") (pinfunction "2Y_6") (pintype "output"))
    )
    (net (code "19") (name "/RBS1") (class "Default")
      (node (ref "3") (pin "14") (pinfunction "OUT_14") (pintype "output"))
      (node (ref "7432_1") (pin "4") (pinfunction "2A_4") (pintype "input"))
      (node (ref "PULL8") (pin "1") (pinfunction "1_1") (pintype "passive"))
    )
    (net (code "20") (name "/RBS2") (class "Default")
      (node (ref "3") (pin "13") (pinfunction "OUT_13") (pintype "output"))
      (node (ref "7432_1") (pin "5") (pinfunction "2B_5") (pintype "input"))
      (node (ref "PULL9") (pin "1") (pinfunction "1_1") (pintype "passive"))
    )
    (net (code "21") (name "/SCS") (class "Default")
      (node (ref "50K9") (pin "A") (pinfunction "A_A") (pintype "passive"))
      (node (ref "50K9") (pin "S") (pinfunction "S_S") (pintype "passive"))
      (node (ref "7432") (pin "11") (pinfunction "4Y_11") (pintype "output"))
      (node (ref "DCNPULL") (pin "2") (pinfunction "2_2") (pintype "passive"))
      (node (ref "DCNRES1") (pin "1") (pinfunction "1_1") (pintype "passive"))
      (node (ref "IC4") (pin "8") (pinfunction "V+_8") (pintype "power_in"))
    )
    (net (code "22") (name "/THR") (class "Default")
      (node (ref "2") (pin "1") (pinfunction "OUT_1") (pintype "output"))
      (node (ref "7408") (pin "1") (pinfunction "1A_1") (pintype "input"))
      (node (ref "PULL3") (pin "1") (pinfunction "1_1") (pintype "passive"))
      (node (ref "TRG-THR") (pin "2") (pinfunction "K_2") (pintype "passive"))
    )
    (net (code "23") (name "/TPS1") (class "Default")
      (node (ref "RES11") (pin "1") (pinfunction "1_1") (pintype "passive"))
      (node (ref "RES12") (pin "1") (pinfunction "1_1") (pintype "passive"))
      (node (ref "RES13") (pin "2") (pinfunction "2_2") (pintype "passive"))
      (node (ref "RES21") (pin "1") (pinfunction "1_1") (pintype "passive"))
      (node (ref "RES22") (pin "1") (pinfunction "1_1") (pintype "passive"))
      (node (ref "RES24") (pin "2") (pinfunction "2_2") (pintype "passive"))
      (node (ref "RES31") (pin "1") (pinfunction "1_1") (pintype "passive"))
      (node (ref "RES32") (pin "1") (pinfunction "1_1") (pintype "passive"))
      (node (ref "RES33") (pin "2") (pinfunction "2_2") (pintype "passive"))
      (node (ref "TPS") (pin "1") (pinfunction "K_1") (pintype "passive"))
    )
    (net (code "24") (name "/TRG") (class "Default")
      (node (ref "7408") (pin "3") (pinfunction "1Y_3") (pintype "output"))
      (node (ref "7432") (pin "10") (pinfunction "3B_10") (pintype "input"))
      (node (ref "TRG-THR") (pin "1") (pinfunction "K_1") (pintype "passive"))
    )
    (net (code "25") (name "/TS1") (class "Default")
      (node (ref "1") (pin "1") (pinfunction "OUT_1") (pintype "output"))
      (node (ref "7432") (pin "1") (pinfunction "1A_1") (pintype "input"))
      (node (ref "PULL1") (pin "1") (pinfunction "1_1") (pintype "passive"))
    )
    (net (code "26") (name "/TS2") (class "Default")
      (node (ref "1") (pin "2") (pinfunction "OUT_2") (pintype "output"))
      (node (ref "7432") (pin "2") (pinfunction "1B_2") (pintype "input"))
      (node (ref "PULL2") (pin "1") (pinfunction "1_1") (pintype "passive"))
    )
    (net (code "27") (name "/TSC") (class "Default")
      (node (ref "7432") (pin "3") (pinfunction "1Y_3") (pintype "output"))
      (node (ref "7432") (pin "9") (pinfunction "3A_9") (pintype "input"))
    )
    (net (code "28") (name "/VCC") (class "Default")
      (node (ref "1") (pin "3") (pinfunction "P$V+_3") (pintype "bidirectional"))
      (node (ref "2") (pin "3") (pinfunction "P$V+_3") (pintype "bidirectional"))
      (node (ref "3") (pin "3") (pinfunction "P$V+_3") (pintype "bidirectional"))
      (node (ref "555RES9") (pin "2") (pinfunction "2_2") (pintype "passive"))
      (node (ref "7404") (pin "14") (pinfunction "VCC_14") (pintype "bidirectional"))
      (node (ref "7408") (pin "14") (pinfunction "VCC_14") (pintype "bidirectional"))
      (node (ref "7432") (pin "14") (pinfunction "VCC_14") (pintype "bidirectional"))
      (node (ref "7432_1") (pin "14") (pinfunction "VCC_14") (pintype "bidirectional"))
      (node (ref "IC5") (pin "4") (pinfunction "~{RST}_4") (pintype "input"))
      (node (ref "IC5") (pin "8") (pinfunction "V+_8") (pintype "power_in"))
      (node (ref "IC7") (pin "3") (pinfunction "VO_3") (pintype "passive"))
      (node (ref "OCTPULL") (pin "2") (pinfunction "2_2") (pintype "passive"))
      (node (ref "POT1") (pin "A") (pinfunction "A_A") (pintype "passive"))
      (node (ref "POT3") (pin "A") (pinfunction "A_A") (pintype "passive"))
      (node (ref "POT4") (pin "A") (pinfunction "A_A") (pintype "passive"))
      (node (ref "POT5") (pin "A") (pinfunction "A_A") (pintype "passive"))
      (node (ref "POT6") (pin "A") (pinfunction "A_A") (pintype "passive"))
      (node (ref "POT8") (pin "A") (pinfunction "A_A") (pintype "passive"))
      (node (ref "POWER") (pin "1") (pinfunction "K_1") (pintype "passive"))
      (node (ref "PULL1") (pin "2") (pinfunction "2_2") (pintype "passive"))
      (node (ref "PULL2") (pin "2") (pinfunction "2_2") (pintype "passive"))
      (node (ref "PULL3") (pin "2") (pinfunction "2_2") (pintype "passive"))
      (node (ref "PULL4") (pin "2") (pinfunction "2_2") (pintype "passive"))
      (node (ref "PULL5") (pin "2") (pinfunction "2_2") (pintype "passive"))
      (node (ref "PULL6") (pin "2") (pinfunction "2_2") (pintype "passive"))
      (node (ref "PULL7") (pin "2") (pinfunction "2_2") (pintype "passive"))
      (node (ref "PULL8") (pin "2") (pinfunction "2_2") (pintype "passive"))
      (node (ref "PULL9") (pin "2") (pinfunction "2_2") (pintype "passive"))
      (node (ref "RES12") (pin "2") (pinfunction "2_2") (pintype "passive"))
      (node (ref "RES22") (pin "2") (pinfunction "2_2") (pintype "passive"))
      (node (ref "RES23") (pin "2") (pinfunction "2_2") (pintype "passive"))
      (node (ref "RES32") (pin "2") (pinfunction "2_2") (pintype "passive"))
      (node (ref "RES42") (pin "2") (pinfunction "2_2") (pintype "passive"))
      (node (ref "RES52") (pin "2") (pinfunction "2_2") (pintype "passive"))
      (node (ref "RES62") (pin "2") (pinfunction "2_2") (pintype "passive"))
      (node (ref "RES72") (pin "2") (pinfunction "2_2") (pintype "passive"))
      (node (ref "RES74") (pin "2") (pinfunction "2_2") (pintype "passive"))
      (node (ref "RES82") (pin "2") (pinfunction "2_2") (pintype "passive"))
      (node (ref "RES92") (pin "2") (pinfunction "2_2") (pintype "passive"))
      (node (ref "RES94") (pin "2") (pinfunction "2_2") (pintype "passive"))
    )
    (net (code "29") (name "Net-(1A-+IN)") (class "Default")
      (node (ref "1") (pin "7") (pinfunction "+IN_7") (pintype "input"))
      (node (ref "RES11") (pin "2") (pinfunction "2_2") (pintype "passive"))
    )
    (net (code "30") (name "Net-(1A--IN)") (class "Default")
      (node (ref "1") (pin "6") (pinfunction "-IN_6") (pintype "input"))
      (node (ref "POT1") (pin "E") (pinfunction "E_E") (pintype "passive"))
      (node (ref "POT1") (pin "S") (pinfunction "S_S") (pintype "passive"))
      (node (ref "RES14") (pin "1") (pinfunction "1_1") (pintype "passive"))
    )
    (net (code "31") (name "Net-(1B-+IN)") (class "Default")
      (node (ref "1") (pin "5") (pinfunction "+IN_5") (pintype "input"))
      (node (ref "POT2") (pin "E") (pinfunction "E_E") (pintype "passive"))
      (node (ref "POT2") (pin "S") (pinfunction "S_S") (pintype "passive"))
      (node (ref "RES23") (pin "1") (pinfunction "1_1") (pintype "passive"))
    )
    (net (code "32") (name "Net-(1B--IN)") (class "Default")
      (node (ref "1") (pin "4") (pinfunction "-IN_4") (pintype "input"))
      (node (ref "RES21") (pin "2") (pinfunction "2_2") (pintype "passive"))
    )
    (net (code "33") (name "Net-(2A-+IN)") (class "Default")
      (node (ref "2") (pin "7") (pinfunction "+IN_7") (pintype "input"))
      (node (ref "RES31") (pin "2") (pinfunction "2_2") (pintype "passive"))
    )
    (net (code "34") (name "Net-(2A--IN)") (class "Default")
      (node (ref "2") (pin "6") (pinfunction "-IN_6") (pintype "input"))
      (node (ref "POT3") (pin "E") (pinfunction "E_E") (pintype "passive"))
      (node (ref "POT3") (pin "S") (pinfunction "S_S") (pintype "passive"))
      (node (ref "RES34") (pin "1") (pinfunction "1_1") (pintype "passive"))
    )
    (net (code "35") (name "Net-(2B-+IN)") (class "Default")
      (node (ref "2") (pin "5") (pinfunction "+IN_5") (pintype "input"))
      (node (ref "RES41") (pin "2") (pinfunction "2_2") (pintype "passive"))
    )
    (net (code "36") (name "Net-(2B--IN)") (class "Default")
      (node (ref "2") (pin "4") (pinfunction "-IN_4") (pintype "input"))
      (node (ref "POT4") (pin "E") (pinfunction "E_E") (pintype "passive"))
      (node (ref "POT4") (pin "S") (pinfunction "S_S") (pintype "passive"))
      (node (ref "RES44") (pin "1") (pinfunction "1_1") (pintype "passive"))
    )
    (net (code "37") (name "Net-(2C-+IN)") (class "Default")
      (node (ref "2") (pin "9") (pinfunction "+IN_9") (pintype "input"))
      (node (ref "RES51") (pin "2") (pinfunction "2_2") (pintype "passive"))
    )
    (net (code "38") (name "Net-(2C--IN)") (class "Default")
      (node (ref "2") (pin "8") (pinfunction "-IN_8") (pintype "input"))
      (node (ref "POT5") (pin "E") (pinfunction "E_E") (pintype "passive"))
      (node (ref "POT5") (pin "S") (pinfunction "S_S") (pintype "passive"))
      (node (ref "RES54") (pin "1") (pinfunction "1_1") (pintype "passive"))
    )
    (net (code "39") (name "Net-(3A-+IN)") (class "Default")
      (node (ref "3") (pin "7") (pinfunction "+IN_7") (pintype "input"))
      (node (ref "RES61") (pin "2") (pinfunction "2_2") (pintype "passive"))
    )
    (net (code "40") (name "Net-(3A--IN)") (class "Default")
      (node (ref "3") (pin "6") (pinfunction "-IN_6") (pintype "input"))
      (node (ref "POT6") (pin "E") (pinfunction "E_E") (pintype "passive"))
      (node (ref "POT6") (pin "S") (pinfunction "S_S") (pintype "passive"))
      (node (ref "RES64") (pin "1") (pinfunction "1_1") (pintype "passive"))
    )
    (net (code "41") (name "Net-(3B-+IN)") (class "Default")
      (node (ref "3") (pin "5") (pinfunction "+IN_5") (pintype "input"))
      (node (ref "POT7") (pin "E") (pinfunction "E_E") (pintype "passive"))
      (node (ref "POT7") (pin "S") (pinfunction "S_S") (pintype "passive"))
      (node (ref "RES74") (pin "1") (pinfunction "1_1") (pintype "passive"))
    )
    (net (code "42") (name "Net-(3B--IN)") (class "Default")
      (node (ref "3") (pin "4") (pinfunction "-IN_4") (pintype "input"))
      (node (ref "RES71") (pin "2") (pinfunction "2_2") (pintype "passive"))
    )
    (net (code "43") (name "Net-(3C-+IN)") (class "Default")
      (node (ref "3") (pin "9") (pinfunction "+IN_9") (pintype "input"))
      (node (ref "RES81") (pin "2") (pinfunction "2_2") (pintype "passive"))
    )
    (net (code "44") (name "Net-(3C--IN)") (class "Default")
      (node (ref "3") (pin "8") (pinfunction "-IN_8") (pintype "input"))
      (node (ref "POT8") (pin "E") (pinfunction "E_E") (pintype "passive"))
      (node (ref "POT8") (pin "S") (pinfunction "S_S") (pintype "passive"))
      (node (ref "RES84") (pin "1") (pinfunction "1_1") (pintype "passive"))
    )
    (net (code "45") (name "Net-(3D-+IN)") (class "Default")
      (node (ref "3") (pin "11") (pinfunction "+IN_11") (pintype "input"))
      (node (ref "POT9") (pin "E") (pinfunction "E_E") (pintype "passive"))
      (node (ref "POT9") (pin "S") (pinfunction "S_S") (pintype "passive"))
      (node (ref "RES94") (pin "1") (pinfunction "1_1") (pintype "passive"))
    )
    (net (code "46") (name "Net-(3D--IN)") (class "Default")
      (node (ref "3") (pin "10") (pinfunction "-IN_10") (pintype "input"))
      (node (ref "RES91") (pin "2") (pinfunction "2_2") (pintype "passive"))
    )
    (net (code "47") (name "Net-(555RES1-Pad2)") (class "Default")
      (node (ref "555RES1") (pin "2") (pinfunction "2_2") (pintype "passive"))
      (node (ref "555RES2") (pin "1") (pinfunction "1_1") (pintype "passive"))
    )
    (net (code "48") (name "Net-(555RES2-Pad2)") (class "Default")
      (node (ref "555RES2") (pin "2") (pinfunction "2_2") (pintype "passive"))
      (node (ref "555RES3") (pin "1") (pinfunction "1_1") (pintype "passive"))
    )
    (net (code "49") (name "Net-(555RES3-Pad2)") (class "Default")
      (node (ref "555RES3") (pin "2") (pinfunction "2_2") (pintype "passive"))
      (node (ref "555RES4") (pin "1") (pinfunction "1_1") (pintype "passive"))
    )
    (net (code "50") (name "Net-(555RES4-Pad2)") (class "Default")
      (node (ref "555RES4") (pin "2") (pinfunction "2_2") (pintype "passive"))
      (node (ref "555RES5") (pin "1") (pinfunction "1_1") (pintype "passive"))
    )
    (net (code "51") (name "Net-(555RES5-Pad2)") (class "Default")
      (node (ref "555RES5") (pin "2") (pinfunction "2_2") (pintype "passive"))
      (node (ref "555RES6") (pin "1") (pinfunction "1_1") (pintype "passive"))
    )
    (net (code "52") (name "Net-(555RES6-Pad2)") (class "Default")
      (node (ref "555RES6") (pin "2") (pinfunction "2_2") (pintype "passive"))
      (node (ref "555RES7") (pin "1") (pinfunction "1_1") (pintype "passive"))
    )
    (net (code "53") (name "Net-(555RES7-Pad2)") (class "Default")
      (node (ref "555RES7") (pin "2") (pinfunction "2_2") (pintype "passive"))
      (node (ref "555RES8") (pin "1") (pinfunction "1_1") (pintype "passive"))
    )
    (net (code "54") (name "Net-(555RES8-Pad2)") (class "Default")
      (node (ref "555RES8") (pin "2") (pinfunction "2_2") (pintype "passive"))
      (node (ref "555RES9") (pin "1") (pinfunction "1_1") (pintype "passive"))
    )
    (net (code "55") (name "Net-(7404-1Y)") (class "Default")
      (node (ref "7404") (pin "2") (pinfunction "1Y_2") (pintype "output"))
      (node (ref "OC2") (pin "1") (pinfunction "A_1") (pintype "passive"))
    )
    (net (code "56") (name "Net-(GREENA-K)") (class "Default")
      (node (ref "GREEN") (pin "1") (pinfunction "K_1") (pintype "passive"))
      (node (ref "OC2") (pin "2") (pinfunction "C_2") (pintype "passive"))
    )
    (net (code "57") (name "Net-(GREENB-K)") (class "Default")
      (node (ref "GREEN") (pin "2") (pinfunction "K_2") (pintype "passive"))
      (node (ref "R57") (pin "2") (pinfunction "2_2") (pintype "passive"))
    )
    (net (code "58") (name "Net-(IC4-+IN)") (class "Default")
      (node (ref "C1-33UF") (pin "1") (pinfunction "1_1") (pintype "passive"))
      (node (ref "DCNRES1") (pin "2") (pinfunction "2_2") (pintype "passive"))
      (node (ref "IC4") (pin "2") (pinfunction "+IN_2") (pintype "input"))
    )
    (net (code "59") (name "Net-(IC4--IN)") (class "Default")
      (node (ref "50K9") (pin "E") (pinfunction "E_E") (pintype "passive"))
      (node (ref "DCNRES2") (pin "1") (pinfunction "1_1") (pintype "passive"))
      (node (ref "IC4") (pin "3") (pinfunction "-IN_3") (pintype "input"))
    )
    (net (code "60") (name "Net-(IC4-ON)") (class "Default")
      (node (ref "IC4") (pin "5") (pinfunction "ON_5") (pintype "passive"))
      (node (ref "IC4") (pin "6") (pinfunction "ON/STR_6") (pintype "passive"))
    )
    (net (code "61") (name "Net-(IC5-CV)") (class "Default")
      (node (ref "C3-0.1UF") (pin "1") (pinfunction "1_1") (pintype "passive"))
      (node (ref "IC5") (pin "5") (pinfunction "CV_5") (pintype "input"))
    )
    (net (code "62") (name "Net-(IC5-DIS)") (class "Default")
      (node (ref "555RES1") (pin "1") (pinfunction "1_1") (pintype "passive"))
      (node (ref "C2-47UF") (pin "1") (pinfunction "1_1") (pintype "passive"))
      (node (ref "IC5") (pin "6") (pinfunction "THR_6") (pintype "input"))
      (node (ref "IC5") (pin "7") (pinfunction "DIS_7") (pintype "input"))
    )
    (net (code "63") (name "Net-(OC2-EMIT)") (class "Default")
      (node (ref "OC2") (pin "3") (pinfunction "EMIT_3") (pintype "passive"))
      (node (ref "U$1") (pin "P$1") (pinfunction "IN_P$1") (pintype "bidirectional"))
    )
    (net (code "64") (name "Net-(REDB-K)") (class "Default")
      (node (ref "R56") (pin "2") (pinfunction "2_2") (pintype "passive"))
      (node (ref "RED") (pin "2") (pinfunction "K_2") (pintype "passive"))
    )
    (net (code "65") (name "unconnected-(1C-+IN-Pad9)") (class "Default")
      (node (ref "1") (pin "9") (pinfunction "+IN_9") (pintype "input"))
    )
    (net (code "66") (name "unconnected-(1C--IN-Pad8)") (class "Default")
      (node (ref "1") (pin "8") (pinfunction "-IN_8") (pintype "input"))
    )
    (net (code "67") (name "unconnected-(1C-OUT-Pad14)") (class "Default")
      (node (ref "1") (pin "14") (pinfunction "OUT_14") (pintype "output"))
    )
    (net (code "68") (name "unconnected-(1D-+IN-Pad11)") (class "Default")
      (node (ref "1") (pin "11") (pinfunction "+IN_11") (pintype "input"))
    )
    (net (code "69") (name "unconnected-(1D--IN-Pad10)") (class "Default")
      (node (ref "1") (pin "10") (pinfunction "-IN_10") (pintype "input"))
    )
    (net (code "70") (name "unconnected-(1D-OUT-Pad13)") (class "Default")
      (node (ref "1") (pin "13") (pinfunction "OUT_13") (pintype "output"))
    )
    (net (code "71") (name "unconnected-(2D-+IN-Pad11)") (class "Default")
      (node (ref "2") (pin "11") (pinfunction "+IN_11") (pintype "input"))
    )
    (net (code "72") (name "unconnected-(2D--IN-Pad10)") (class "Default")
      (node (ref "2") (pin "10") (pinfunction "-IN_10") (pintype "input"))
    )
    (net (code "73") (name "unconnected-(2D-OUT-Pad13)") (class "Default")
      (node (ref "2") (pin "13") (pinfunction "OUT_13") (pintype "output"))
    )
    (net (code "74") (name "unconnected-(7404-2A-Pad3)") (class "Default")
      (node (ref "7404") (pin "3") (pinfunction "2A_3") (pintype "input"))
    )
    (net (code "75") (name "unconnected-(7404-2Y-Pad4)") (class "Default")
      (node (ref "7404") (pin "4") (pinfunction "2Y_4") (pintype "output"))
    )
    (net (code "76") (name "unconnected-(7404-3A-Pad5)") (class "Default")
      (node (ref "7404") (pin "5") (pinfunction "3A_5") (pintype "input"))
    )
    (net (code "77") (name "unconnected-(7404-3Y-Pad6)") (class "Default")
      (node (ref "7404") (pin "6") (pinfunction "3Y_6") (pintype "output"))
    )
    (net (code "78") (name "unconnected-(7404-4A-Pad9)") (class "Default")
      (node (ref "7404") (pin "9") (pinfunction "4A_9") (pintype "input"))
    )
    (net (code "79") (name "unconnected-(7404-4Y-Pad8)") (class "Default")
      (node (ref "7404") (pin "8") (pinfunction "4Y_8") (pintype "output"))
    )
    (net (code "80") (name "unconnected-(7404-5A-Pad11)") (class "Default")
      (node (ref "7404") (pin "11") (pinfunction "5A_11") (pintype "input"))
    )
    (net (code "81") (name "unconnected-(7404-5Y-Pad10)") (class "Default")
      (node (ref "7404") (pin "10") (pinfunction "5Y_10") (pintype "output"))
    )
    (net (code "82") (name "unconnected-(7404-6A-Pad13)") (class "Default")
      (node (ref "7404") (pin "13") (pinfunction "6A_13") (pintype "input"))
    )
    (net (code "83") (name "unconnected-(7404-6Y-Pad12)") (class "Default")
      (node (ref "7404") (pin "12") (pinfunction "6Y_12") (pintype "output"))
    )
    (net (code "84") (name "unconnected-(7408-2A-Pad4)") (class "Default")
      (node (ref "7408") (pin "4") (pinfunction "2A_4") (pintype "input"))
    )
    (net (code "85") (name "unconnected-(7408-2B-Pad5)") (class "Default")
      (node (ref "7408") (pin "5") (pinfunction "2B_5") (pintype "input"))
    )
    (net (code "86") (name "unconnected-(7408-2Y-Pad6)") (class "Default")
      (node (ref "7408") (pin "6") (pinfunction "2Y_6") (pintype "output"))
    )
    (net (code "87") (name "unconnected-(7408-3A-Pad9)") (class "Default")
      (node (ref "7408") (pin "9") (pinfunction "3A_9") (pintype "input"))
    )
    (net (code "88") (name "unconnected-(7408-3B-Pad10)") (class "Default")
      (node (ref "7408") (pin "10") (pinfunction "3B_10") (pintype "input"))
    )
    (net (code "89") (name "unconnected-(7408-3Y-Pad8)") (class "Default")
      (node (ref "7408") (pin "8") (pinfunction "3Y_8") (pintype "output"))
    )
    (net (code "90") (name "unconnected-(7408-4A-Pad12)") (class "Default")
      (node (ref "7408") (pin "12") (pinfunction "4A_12") (pintype "input"))
    )
    (net (code "91") (name "unconnected-(7408-4B-Pad13)") (class "Default")
      (node (ref "7408") (pin "13") (pinfunction "4B_13") (pintype "input"))
    )
    (net (code "92") (name "unconnected-(7408-4Y-Pad11)") (class "Default")
      (node (ref "7408") (pin "11") (pinfunction "4Y_11") (pintype "output"))
    )
    (net (code "93") (name "unconnected-(7432_1-4A-Pad12)") (class "Default")
      (node (ref "7432_1") (pin "12") (pinfunction "4A_12") (pintype "input"))
    )
    (net (code "94") (name "unconnected-(7432_1-4B-Pad13)") (class "Default")
      (node (ref "7432_1") (pin "13") (pinfunction "4B_13") (pintype "input"))
    )
    (net (code "95") (name "unconnected-(7432_1-4Y-Pad11)") (class "Default")
      (node (ref "7432_1") (pin "11") (pinfunction "4Y_11") (pintype "output"))
    )
    (net (code "96") (name "unconnected-(U$1-COM-OPEN-PadCOM_CPEN)") (class "Default")
      (node (ref "U$1") (pin "COM_CPEN") (pinfunction "COM-OPEN_COM_CPEN") (pintype "bidirectional"))
    )
  )
)
